# Water_Sensor.net
KiCad netlist of a schematic drawn in EasyEDA
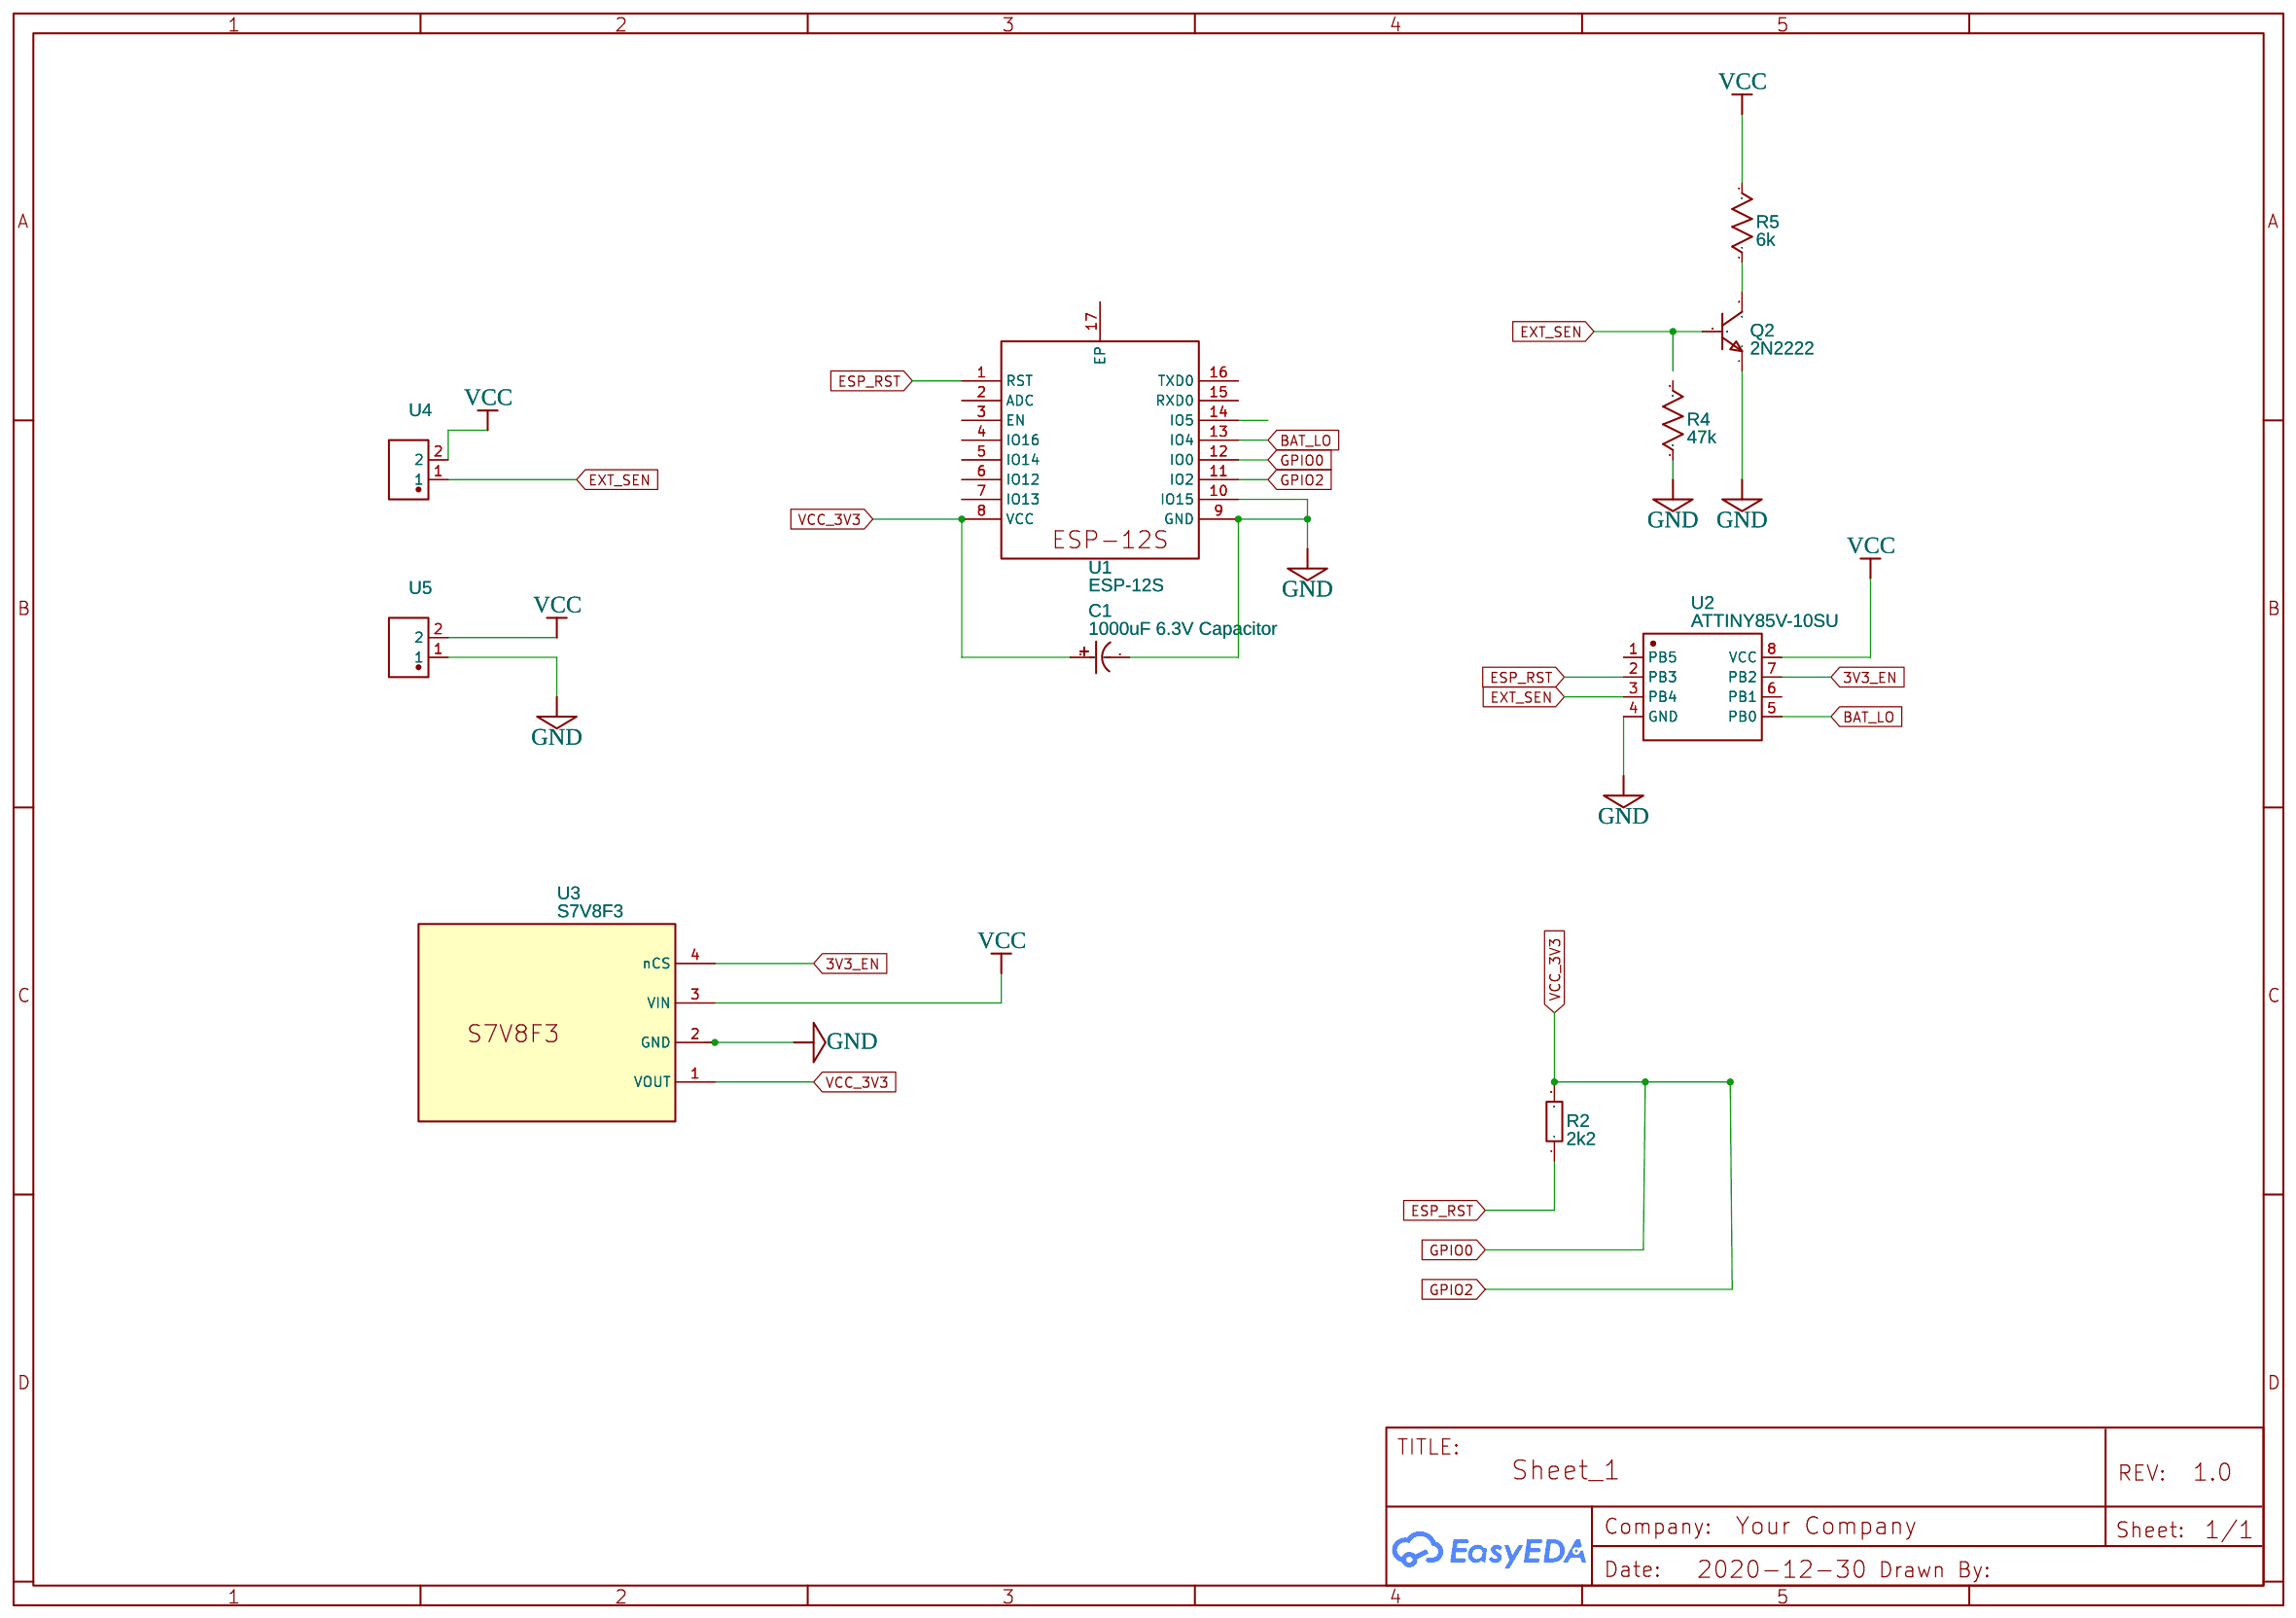
[diagram p0: schematic sheet]

(export (version "E")
  (design (tool "Eeschema 10.0.6"))
  (components
    (comp (ref "C1") (value "1000uF 6.3V Capacitor") (libsource (lib "") (part "1000uF 6.3V Capacitor")))
    (comp (ref "Q2")
      (value "2N2222")
      (fields (field (name "BOM_Supplier Part") "C118536"))
      (libsource (lib "") (part "2N2222"))
    )
    (comp (ref "R2")
      (value "2k2")
      (fields
        (field (name "BOM_Manufacturer Part") "CFR02SJ0220A10")
        (field (name "BOM_Supplier Part") "C69874")
      )
      (libsource (lib "") (part "2k2"))
    )
    (comp (ref "R4") (value "47k") (libsource (lib "") (part "R_0603_US")))
    (comp (ref "R5") (value "6k") (libsource (lib "") (part "R_0603_US")))
    (comp (ref "U1")
      (value "ESP-12S")
      (fields (field (name "BOM_Supplier Part") "C82898"))
      (libsource (lib "") (part "ESP-12S"))
    )
    (comp (ref "U2")
      (value "ATTINY85V-10SU")
      (fields (field (name "BOM_Supplier Part") "C152192"))
      (libsource (lib "") (part "ATTINY85V-10SU"))
    )
    (comp (ref "U3") (value "S7V8F3") (libsource (lib "") (part "S7V8F3")))
    (comp (ref "U4")
      (value "XY301V-A-5.0-2P")
      (fields (field (name "BOM_Supplier Part") "C557651"))
      (libsource (lib "") (part "XY301V-A-5.0-2P"))
    )
    (comp (ref "U5")
      (value "XY301V-A-5.0-2P")
      (fields (field (name "BOM_Supplier Part") "C557651"))
      (libsource (lib "") (part "XY301V-A-5.0-2P"))
    )
  )
  (nets
    (net (code "1") (name "3V3_EN") (class "Default")
      (node (ref "U2") (pin "7") (pinfunction "PB2_7") (pintype "unspecified"))
      (node (ref "U3") (pin "4") (pinfunction "nCS_4") (pintype "unspecified"))
    )
    (net (code "2") (name "BAT_LO") (class "Default")
      (node (ref "U1") (pin "13") (pinfunction "IO4_13") (pintype "unspecified"))
      (node (ref "U2") (pin "5") (pinfunction "PB0_5") (pintype "unspecified"))
    )
    (net (code "3") (name "ESP_RST") (class "Default")
      (node (ref "R2") (pin "1") (pinfunction "1_1") (pintype "input"))
      (node (ref "U1") (pin "1") (pinfunction "RST_1") (pintype "unspecified"))
      (node (ref "U2") (pin "2") (pinfunction "PB3_2") (pintype "unspecified"))
    )
    (net (code "4") (name "EXT_SEN") (class "Default")
      (node (ref "Q2") (pin "2") (pinfunction "B_2") (pintype "unspecified"))
      (node (ref "U2") (pin "3") (pinfunction "PB4_3") (pintype "unspecified"))
      (node (ref "U4") (pin "1") (pinfunction "1_1") (pintype "unspecified"))
    )
    (net (code "5") (name "GND") (class "Default")
      (node (ref "C1") (pin "2") (pinfunction "2_2") (pintype "input"))
      (node (ref "Q2") (pin "1") (pinfunction "E_1") (pintype "unspecified"))
      (node (ref "R4") (pin "1") (pinfunction "1_1") (pintype "unspecified"))
      (node (ref "U1") (pin "10") (pinfunction "IO15_10") (pintype "unspecified"))
      (node (ref "U1") (pin "9") (pinfunction "GND_9") (pintype "unspecified"))
      (node (ref "U2") (pin "4") (pinfunction "GND_4") (pintype "unspecified"))
      (node (ref "U3") (pin "2") (pinfunction "GND_2") (pintype "unspecified"))
      (node (ref "U5") (pin "1") (pinfunction "1_1") (pintype "unspecified"))
    )
    (net (code "6") (name "GPIO0") (class "Default")
      (node (ref "C1") (pin "1") (pinfunction "1_1") (pintype "input"))
      (node (ref "R2") (pin "2") (pinfunction "2_2") (pintype "input"))
      (node (ref "U1") (pin "11") (pinfunction "IO2_11") (pintype "unspecified"))
      (node (ref "U1") (pin "12") (pinfunction "IO0_12") (pintype "unspecified"))
      (node (ref "U1") (pin "8") (pinfunction "VCC_8") (pintype "unspecified"))
      (node (ref "U3") (pin "1") (pinfunction "VOUT_1") (pintype "unspecified"))
    )
    (net (code "7") (name "Net-(Q2-C)") (class "Default")
      (node (ref "Q2") (pin "3") (pinfunction "C_3") (pintype "unspecified"))
      (node (ref "R5") (pin "1") (pinfunction "1_1") (pintype "unspecified"))
    )
    (net (code "8") (name "VCC") (class "Default")
      (node (ref "R5") (pin "2") (pinfunction "2_2") (pintype "unspecified"))
      (node (ref "U2") (pin "8") (pinfunction "VCC_8") (pintype "unspecified"))
      (node (ref "U3") (pin "3") (pinfunction "VIN_3") (pintype "unspecified"))
      (node (ref "U4") (pin "2") (pinfunction "2_2") (pintype "unspecified"))
      (node (ref "U5") (pin "2") (pinfunction "2_2") (pintype "unspecified"))
    )
    (net (code "9") (name "unconnected-(R4-Pad2)") (class "Default")
      (node (ref "R4") (pin "2") (pinfunction "2_2") (pintype "unspecified"))
    )
    (net (code "10") (name "unconnected-(U1-ADC-Pad2)") (class "Default")
      (node (ref "U1") (pin "2") (pinfunction "ADC_2") (pintype "unspecified"))
    )
    (net (code "11") (name "unconnected-(U1-EN-Pad3)") (class "Default")
      (node (ref "U1") (pin "3") (pinfunction "EN_3") (pintype "unspecified"))
    )
    (net (code "12") (name "unconnected-(U1-EP-Pad17)") (class "Default")
      (node (ref "U1") (pin "17") (pinfunction "EP_17") (pintype "unspecified"))
    )
    (net (code "13") (name "unconnected-(U1-IO5-Pad14)") (class "Default")
      (node (ref "U1") (pin "14") (pinfunction "IO5_14") (pintype "unspecified"))
    )
    (net (code "14") (name "unconnected-(U1-IO12-Pad6)") (class "Default")
      (node (ref "U1") (pin "6") (pinfunction "IO12_6") (pintype "unspecified"))
    )
    (net (code "15") (name "unconnected-(U1-IO13-Pad7)") (class "Default")
      (node (ref "U1") (pin "7") (pinfunction "IO13_7") (pintype "unspecified"))
    )
    (net (code "16") (name "unconnected-(U1-IO14-Pad5)") (class "Default")
      (node (ref "U1") (pin "5") (pinfunction "IO14_5") (pintype "unspecified"))
    )
    (net (code "17") (name "unconnected-(U1-IO16-Pad4)") (class "Default")
      (node (ref "U1") (pin "4") (pinfunction "IO16_4") (pintype "unspecified"))
    )
    (net (code "18") (name "unconnected-(U1-RXD0-Pad15)") (class "Default")
      (node (ref "U1") (pin "15") (pinfunction "RXD0_15") (pintype "unspecified"))
    )
    (net (code "19") (name "unconnected-(U1-TXD0-Pad16)") (class "Default")
      (node (ref "U1") (pin "16") (pinfunction "TXD0_16") (pintype "unspecified"))
    )
    (net (code "20") (name "unconnected-(U2-PB1-Pad6)") (class "Default")
      (node (ref "U2") (pin "6") (pinfunction "PB1_6") (pintype "unspecified"))
    )
    (net (code "21") (name "unconnected-(U2-PB5-Pad1)") (class "Default")
      (node (ref "U2") (pin "1") (pinfunction "PB5_1") (pintype "unspecified"))
    )
  )
)
